# OSO-MISC-21-017_Sensor_Watch_Flash.net
KiCad netlist of a schematic drawn in EAGLE
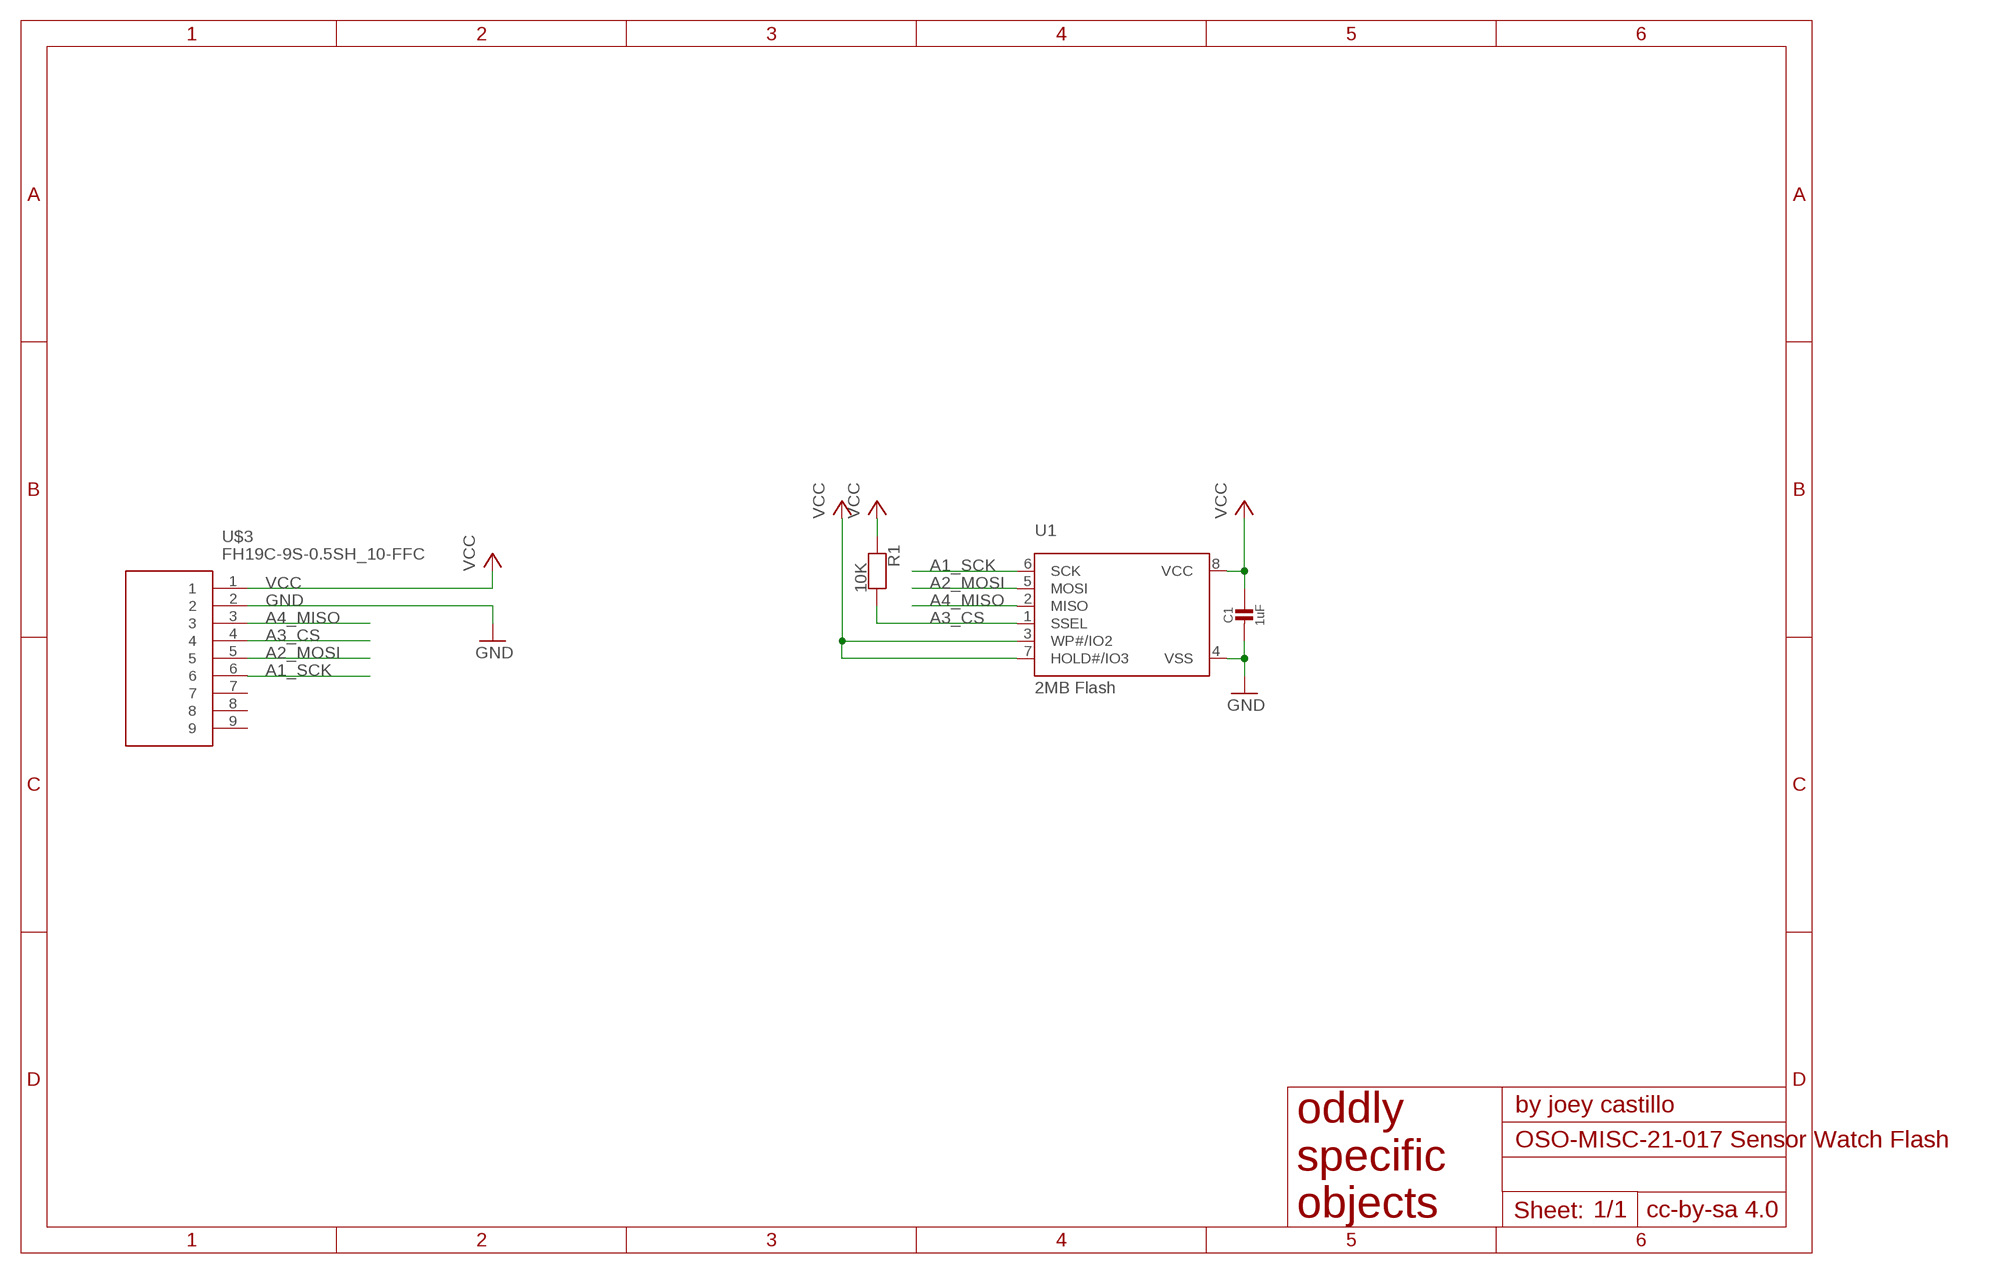
[diagram p0: schematic, sheet 1]

(export (version "E")
  (design (tool "Eeschema 10.0.6"))
  (components
    (comp (ref "C1")
      (value "1uF")
      (footprint "eagle-import:_0603MP")
      (libsource (lib "eagle-import") (part "CAP_CERAMIC_0603MP"))
    )
    (comp (ref "R1")
      (value "10K")
      (footprint "eagle-import:_0603MP")
      (libsource (lib "eagle-import") (part "RESISTOR_0603MP"))
    )
    (comp (ref "U$3")
      (value "FH19C-9S-0.5SH_10-FFC")
      (footprint "eagle-import:FH19C9S05SH10-FFC")
      (libsource (lib "eagle-import") (part "FH19C-9S-0.5SH_10-FFC"))
    )
    (comp (ref "U1")
      (value "2MB Flash")
      (footprint "eagle-import:USON8")
      (libsource (lib "eagle-import") (part "SPIFLASH_8PINUX"))
    )
  )
  (nets
    (net (code "1") (name "/A1_SCK") (class "Default")
      (node (ref "U$3") (pin "6") (pinfunction "6_6") (pintype "bidirectional"))
      (node (ref "U1") (pin "6") (pinfunction "SCK_6") (pintype "bidirectional"))
    )
    (net (code "2") (name "/A2_MOSI") (class "Default")
      (node (ref "U$3") (pin "5") (pinfunction "5_5") (pintype "bidirectional"))
      (node (ref "U1") (pin "5") (pinfunction "MOSI_5") (pintype "bidirectional"))
    )
    (net (code "3") (name "/A3_CS") (class "Default")
      (node (ref "R1") (pin "2") (pinfunction "2_2") (pintype "passive"))
      (node (ref "U$3") (pin "4") (pinfunction "4_4") (pintype "bidirectional"))
      (node (ref "U1") (pin "1") (pinfunction "SSEL_1") (pintype "bidirectional"))
    )
    (net (code "4") (name "/A4_MISO") (class "Default")
      (node (ref "U$3") (pin "3") (pinfunction "3_3") (pintype "bidirectional"))
      (node (ref "U1") (pin "2") (pinfunction "MISO_2") (pintype "bidirectional"))
    )
    (net (code "5") (name "GND") (class "Default")
      (node (ref "C1") (pin "2") (pinfunction "2_2") (pintype "passive"))
      (node (ref "U$3") (pin "2") (pinfunction "2_2") (pintype "bidirectional"))
      (node (ref "U1") (pin "4") (pinfunction "VSS_4") (pintype "bidirectional"))
    )
    (net (code "6") (name "VCC") (class "Default")
      (node (ref "C1") (pin "1") (pinfunction "1_1") (pintype "passive"))
      (node (ref "R1") (pin "1") (pinfunction "1_1") (pintype "passive"))
      (node (ref "U$3") (pin "1") (pinfunction "1_1") (pintype "bidirectional"))
      (node (ref "U1") (pin "3") (pinfunction "WP#/IO2_3") (pintype "bidirectional"))
      (node (ref "U1") (pin "7") (pinfunction "HOLD#/IO3_7") (pintype "bidirectional"))
      (node (ref "U1") (pin "8") (pinfunction "VCC_8") (pintype "bidirectional"))
    )
    (net (code "7") (name "unconnected-(U$3-Pad7)") (class "Default")
      (node (ref "U$3") (pin "7") (pinfunction "7_7") (pintype "bidirectional"))
    )
    (net (code "8") (name "unconnected-(U$3-Pad8)") (class "Default")
      (node (ref "U$3") (pin "8") (pinfunction "8_8") (pintype "bidirectional"))
    )
    (net (code "9") (name "unconnected-(U$3-Pad9)") (class "Default")
      (node (ref "U$3") (pin "9") (pinfunction "9_9") (pintype "bidirectional"))
    )
  )
)
